# MicConnectros.net
KiCad netlist of a schematic drawn in Altium Designer
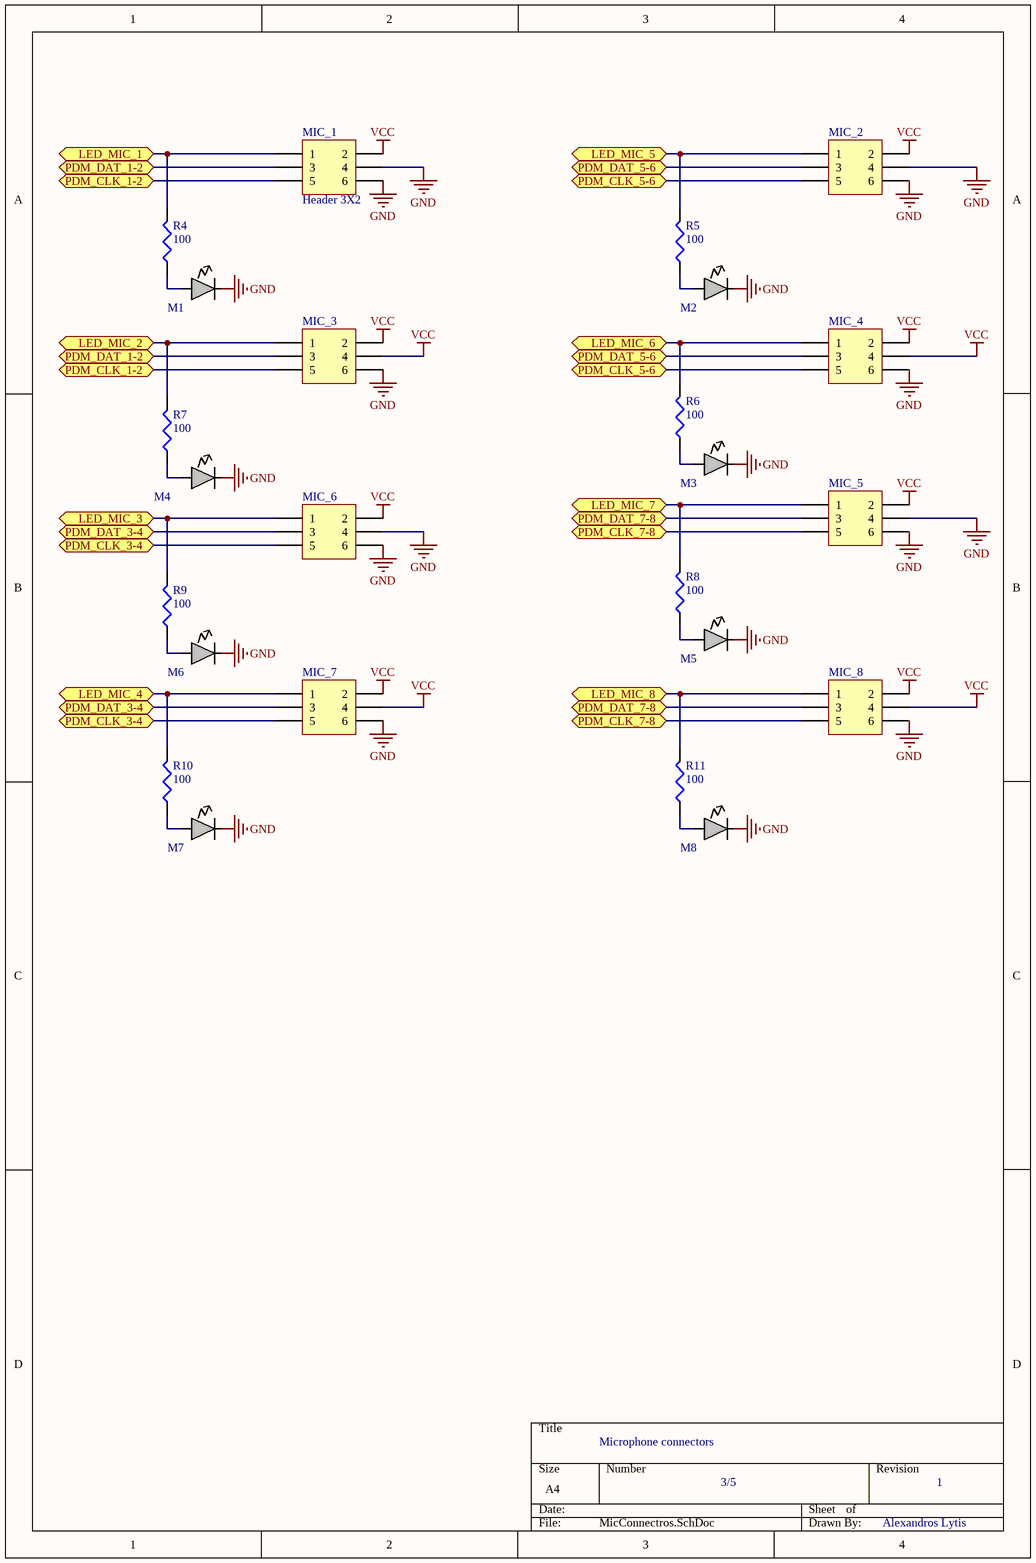
[diagram p0: MicConnectros.SchDoc]

(export (version "E")
  (design (tool "Eeschema 10.0.6"))
  (components
    (comp (ref "M1")
      (value "LED_1.6x0.8mm")
      (footprint "J1-0603")
      (libsource (lib "Custom_Libraries") (part "LED_1.6x0.8mm"))
    )
    (comp (ref "M2")
      (value "LED_1.6x0.8mm")
      (footprint "J1-0603")
      (libsource (lib "Custom_Libraries") (part "LED_1.6x0.8mm"))
    )
    (comp (ref "M3")
      (value "LED_1.6x0.8mm")
      (footprint "J1-0603")
      (libsource (lib "Custom_Libraries") (part "LED_1.6x0.8mm"))
    )
    (comp (ref "M4")
      (value "LED_1.6x0.8mm")
      (footprint "J1-0603")
      (libsource (lib "Custom_Libraries") (part "LED_1.6x0.8mm"))
    )
    (comp (ref "M5")
      (value "LED_1.6x0.8mm")
      (footprint "J1-0603")
      (libsource (lib "Custom_Libraries") (part "LED_1.6x0.8mm"))
    )
    (comp (ref "M6")
      (value "LED_1.6x0.8mm")
      (footprint "J1-0603")
      (libsource (lib "Custom_Libraries") (part "LED_1.6x0.8mm"))
    )
    (comp (ref "M7")
      (value "LED_1.6x0.8mm")
      (footprint "J1-0603")
      (libsource (lib "Custom_Libraries") (part "LED_1.6x0.8mm"))
    )
    (comp (ref "M8")
      (value "LED_1.6x0.8mm")
      (footprint "J1-0603")
      (libsource (lib "Custom_Libraries") (part "LED_1.6x0.8mm"))
    )
    (comp (ref "MIC_1")
      (value "Header 3X2")
      (footprint "HDR2X3")
      (description "Header, 3-Pin, Dual row")
      (fields (field (name "PUBLISHER") "Altium Limited"))
      (libsource (lib "Miscellaneous Connectors") (part "Header 3X2"))
    )
    (comp (ref "MIC_2")
      (value "Header 3X2")
      (footprint "HDR2X3")
      (description "Header, 3-Pin, Dual row")
      (fields (field (name "PUBLISHER") "Altium Limited"))
      (libsource (lib "Miscellaneous Connectors") (part "Header 3X2"))
    )
    (comp (ref "MIC_3")
      (value "Header 3X2")
      (footprint "HDR2X3")
      (description "Header, 3-Pin, Dual row")
      (fields (field (name "PUBLISHER") "Altium Limited"))
      (libsource (lib "Miscellaneous Connectors") (part "Header 3X2"))
    )
    (comp (ref "MIC_4")
      (value "Header 3X2")
      (footprint "HDR2X3")
      (description "Header, 3-Pin, Dual row")
      (fields (field (name "PUBLISHER") "Altium Limited"))
      (libsource (lib "Miscellaneous Connectors") (part "Header 3X2"))
    )
    (comp (ref "MIC_5")
      (value "Header 3X2")
      (footprint "HDR2X3")
      (description "Header, 3-Pin, Dual row")
      (fields (field (name "PUBLISHER") "Altium Limited"))
      (libsource (lib "Miscellaneous Connectors") (part "Header 3X2"))
    )
    (comp (ref "MIC_6")
      (value "Header 3X2")
      (footprint "HDR2X3")
      (description "Header, 3-Pin, Dual row")
      (fields (field (name "PUBLISHER") "Altium Limited"))
      (libsource (lib "Miscellaneous Connectors") (part "Header 3X2"))
    )
    (comp (ref "MIC_7")
      (value "Header 3X2")
      (footprint "HDR2X3")
      (description "Header, 3-Pin, Dual row")
      (fields (field (name "PUBLISHER") "Altium Limited"))
      (libsource (lib "Miscellaneous Connectors") (part "Header 3X2"))
    )
    (comp (ref "MIC_8")
      (value "Header 3X2")
      (footprint "HDR2X3")
      (description "Header, 3-Pin, Dual row")
      (fields (field (name "PUBLISHER") "Altium Limited"))
      (libsource (lib "Miscellaneous Connectors") (part "Header 3X2"))
    )
    (comp (ref "R4")
      (value "100")
      (footprint "RES0603")
      (description "Resistor")
      (fields (field (name "Comment") "Res3") (field (name "PUBLISHER") "Altium Limited"))
      (libsource (lib "Miscellaneous Devices") (part "Res3"))
    )
    (comp (ref "R5")
      (value "100")
      (footprint "RES0603")
      (description "Resistor")
      (fields (field (name "Comment") "Res3") (field (name "PUBLISHER") "Altium Limited"))
      (libsource (lib "Miscellaneous Devices") (part "Res3"))
    )
    (comp (ref "R6")
      (value "100")
      (footprint "RES0603")
      (description "Resistor")
      (fields (field (name "Comment") "Res3") (field (name "PUBLISHER") "Altium Limited"))
      (libsource (lib "Miscellaneous Devices") (part "Res3"))
    )
    (comp (ref "R7")
      (value "100")
      (footprint "RES0603")
      (description "Resistor")
      (fields (field (name "Comment") "Res3") (field (name "PUBLISHER") "Altium Limited"))
      (libsource (lib "Miscellaneous Devices") (part "Res3"))
    )
    (comp (ref "R8")
      (value "100")
      (footprint "RES0603")
      (description "Resistor")
      (fields (field (name "Comment") "Res3") (field (name "PUBLISHER") "Altium Limited"))
      (libsource (lib "Miscellaneous Devices") (part "Res3"))
    )
    (comp (ref "R9")
      (value "100")
      (footprint "RES0603")
      (description "Resistor")
      (fields (field (name "Comment") "Res3") (field (name "PUBLISHER") "Altium Limited"))
      (libsource (lib "Miscellaneous Devices") (part "Res3"))
    )
    (comp (ref "R10")
      (value "100")
      (footprint "RES0603")
      (description "Resistor")
      (fields (field (name "Comment") "Res3") (field (name "PUBLISHER") "Altium Limited"))
      (libsource (lib "Miscellaneous Devices") (part "Res3"))
    )
    (comp (ref "R11")
      (value "100")
      (footprint "RES0603")
      (description "Resistor")
      (fields (field (name "Comment") "Res3") (field (name "PUBLISHER") "Altium Limited"))
      (libsource (lib "Miscellaneous Devices") (part "Res3"))
    )
  )
  (nets
    (net (code "1") (name "/LED_MIC_1") (class "Default")
      (node (ref "MIC_1") (pin "1") (pinfunction "1_1") (pintype "passive"))
      (node (ref "R4") (pin "2") (pinfunction "2_2") (pintype "passive"))
    )
    (net (code "2") (name "/LED_MIC_2") (class "Default")
      (node (ref "MIC_3") (pin "1") (pinfunction "1_1") (pintype "passive"))
      (node (ref "R7") (pin "2") (pinfunction "2_2") (pintype "passive"))
    )
    (net (code "3") (name "/LED_MIC_3") (class "Default")
      (node (ref "MIC_6") (pin "1") (pinfunction "1_1") (pintype "passive"))
      (node (ref "R9") (pin "2") (pinfunction "2_2") (pintype "passive"))
    )
    (net (code "4") (name "/LED_MIC_4") (class "Default")
      (node (ref "MIC_7") (pin "1") (pinfunction "1_1") (pintype "passive"))
      (node (ref "R10") (pin "2") (pinfunction "2_2") (pintype "passive"))
    )
    (net (code "5") (name "/LED_MIC_5") (class "Default")
      (node (ref "MIC_2") (pin "1") (pinfunction "1_1") (pintype "passive"))
      (node (ref "R5") (pin "2") (pinfunction "2_2") (pintype "passive"))
    )
    (net (code "6") (name "/LED_MIC_6") (class "Default")
      (node (ref "MIC_4") (pin "1") (pinfunction "1_1") (pintype "passive"))
      (node (ref "R6") (pin "2") (pinfunction "2_2") (pintype "passive"))
    )
    (net (code "7") (name "/LED_MIC_7") (class "Default")
      (node (ref "MIC_5") (pin "1") (pinfunction "1_1") (pintype "passive"))
      (node (ref "R8") (pin "2") (pinfunction "2_2") (pintype "passive"))
    )
    (net (code "8") (name "/LED_MIC_8") (class "Default")
      (node (ref "MIC_8") (pin "1") (pinfunction "1_1") (pintype "passive"))
      (node (ref "R11") (pin "2") (pinfunction "2_2") (pintype "passive"))
    )
    (net (code "9") (name "/PDM_CLK_1-2") (class "Default")
      (node (ref "MIC_1") (pin "5") (pinfunction "5_5") (pintype "passive"))
      (node (ref "MIC_3") (pin "5") (pinfunction "5_5") (pintype "passive"))
    )
    (net (code "10") (name "/PDM_CLK_3-4") (class "Default")
      (node (ref "MIC_6") (pin "5") (pinfunction "5_5") (pintype "passive"))
      (node (ref "MIC_7") (pin "5") (pinfunction "5_5") (pintype "passive"))
    )
    (net (code "11") (name "/PDM_CLK_5-6") (class "Default")
      (node (ref "MIC_2") (pin "5") (pinfunction "5_5") (pintype "passive"))
      (node (ref "MIC_4") (pin "5") (pinfunction "5_5") (pintype "passive"))
    )
    (net (code "12") (name "/PDM_CLK_7-8") (class "Default")
      (node (ref "MIC_5") (pin "5") (pinfunction "5_5") (pintype "passive"))
      (node (ref "MIC_8") (pin "5") (pinfunction "5_5") (pintype "passive"))
    )
    (net (code "13") (name "/PDM_DAT_1-2") (class "Default")
      (node (ref "MIC_1") (pin "3") (pinfunction "3_3") (pintype "passive"))
      (node (ref "MIC_3") (pin "3") (pinfunction "3_3") (pintype "passive"))
    )
    (net (code "14") (name "/PDM_DAT_3-4") (class "Default")
      (node (ref "MIC_6") (pin "3") (pinfunction "3_3") (pintype "passive"))
      (node (ref "MIC_7") (pin "3") (pinfunction "3_3") (pintype "passive"))
    )
    (net (code "15") (name "/PDM_DAT_5-6") (class "Default")
      (node (ref "MIC_2") (pin "3") (pinfunction "3_3") (pintype "passive"))
      (node (ref "MIC_4") (pin "3") (pinfunction "3_3") (pintype "passive"))
    )
    (net (code "16") (name "/PDM_DAT_7-8") (class "Default")
      (node (ref "MIC_5") (pin "3") (pinfunction "3_3") (pintype "passive"))
      (node (ref "MIC_8") (pin "3") (pinfunction "3_3") (pintype "passive"))
    )
    (net (code "17") (name "GND") (class "Default")
      (node (ref "M1") (pin "2") (pintype "passive"))
      (node (ref "M2") (pin "2") (pintype "passive"))
      (node (ref "M3") (pin "2") (pintype "passive"))
      (node (ref "M4") (pin "2") (pintype "passive"))
      (node (ref "M5") (pin "2") (pintype "passive"))
      (node (ref "M6") (pin "2") (pintype "passive"))
      (node (ref "M7") (pin "2") (pintype "passive"))
      (node (ref "M8") (pin "2") (pintype "passive"))
      (node (ref "MIC_1") (pin "4") (pinfunction "4_4") (pintype "passive"))
      (node (ref "MIC_1") (pin "6") (pinfunction "6_6") (pintype "passive"))
      (node (ref "MIC_2") (pin "4") (pinfunction "4_4") (pintype "passive"))
      (node (ref "MIC_2") (pin "6") (pinfunction "6_6") (pintype "passive"))
      (node (ref "MIC_3") (pin "6") (pinfunction "6_6") (pintype "passive"))
      (node (ref "MIC_4") (pin "6") (pinfunction "6_6") (pintype "passive"))
      (node (ref "MIC_5") (pin "4") (pinfunction "4_4") (pintype "passive"))
      (node (ref "MIC_5") (pin "6") (pinfunction "6_6") (pintype "passive"))
      (node (ref "MIC_6") (pin "4") (pinfunction "4_4") (pintype "passive"))
      (node (ref "MIC_6") (pin "6") (pinfunction "6_6") (pintype "passive"))
      (node (ref "MIC_7") (pin "6") (pinfunction "6_6") (pintype "passive"))
      (node (ref "MIC_8") (pin "6") (pinfunction "6_6") (pintype "passive"))
    )
    (net (code "18") (name "Net-(M1-Pad1)") (class "Default")
      (node (ref "M1") (pin "1") (pintype "passive"))
      (node (ref "R4") (pin "1") (pinfunction "1_1") (pintype "passive"))
    )
    (net (code "19") (name "Net-(M2-Pad1)") (class "Default")
      (node (ref "M2") (pin "1") (pintype "passive"))
      (node (ref "R5") (pin "1") (pinfunction "1_1") (pintype "passive"))
    )
    (net (code "20") (name "Net-(M3-Pad1)") (class "Default")
      (node (ref "M3") (pin "1") (pintype "passive"))
      (node (ref "R6") (pin "1") (pinfunction "1_1") (pintype "passive"))
    )
    (net (code "21") (name "Net-(M4-Pad1)") (class "Default")
      (node (ref "M4") (pin "1") (pintype "passive"))
      (node (ref "R7") (pin "1") (pinfunction "1_1") (pintype "passive"))
    )
    (net (code "22") (name "Net-(M5-Pad1)") (class "Default")
      (node (ref "M5") (pin "1") (pintype "passive"))
      (node (ref "R8") (pin "1") (pinfunction "1_1") (pintype "passive"))
    )
    (net (code "23") (name "Net-(M6-Pad1)") (class "Default")
      (node (ref "M6") (pin "1") (pintype "passive"))
      (node (ref "R9") (pin "1") (pinfunction "1_1") (pintype "passive"))
    )
    (net (code "24") (name "Net-(M7-Pad1)") (class "Default")
      (node (ref "M7") (pin "1") (pintype "passive"))
      (node (ref "R10") (pin "1") (pinfunction "1_1") (pintype "passive"))
    )
    (net (code "25") (name "Net-(M8-Pad1)") (class "Default")
      (node (ref "M8") (pin "1") (pintype "passive"))
      (node (ref "R11") (pin "1") (pinfunction "1_1") (pintype "passive"))
    )
    (net (code "26") (name "VCC") (class "Default")
      (node (ref "MIC_1") (pin "2") (pinfunction "2_2") (pintype "passive"))
      (node (ref "MIC_2") (pin "2") (pinfunction "2_2") (pintype "passive"))
      (node (ref "MIC_3") (pin "2") (pinfunction "2_2") (pintype "passive"))
      (node (ref "MIC_3") (pin "4") (pinfunction "4_4") (pintype "passive"))
      (node (ref "MIC_4") (pin "2") (pinfunction "2_2") (pintype "passive"))
      (node (ref "MIC_4") (pin "4") (pinfunction "4_4") (pintype "passive"))
      (node (ref "MIC_5") (pin "2") (pinfunction "2_2") (pintype "passive"))
      (node (ref "MIC_6") (pin "2") (pinfunction "2_2") (pintype "passive"))
      (node (ref "MIC_7") (pin "2") (pinfunction "2_2") (pintype "passive"))
      (node (ref "MIC_7") (pin "4") (pinfunction "4_4") (pintype "passive"))
      (node (ref "MIC_8") (pin "2") (pinfunction "2_2") (pintype "passive"))
      (node (ref "MIC_8") (pin "4") (pinfunction "4_4") (pintype "passive"))
    )
  )
)
